# FunControler.net
KiCad netlist of a schematic drawn in EAGLE
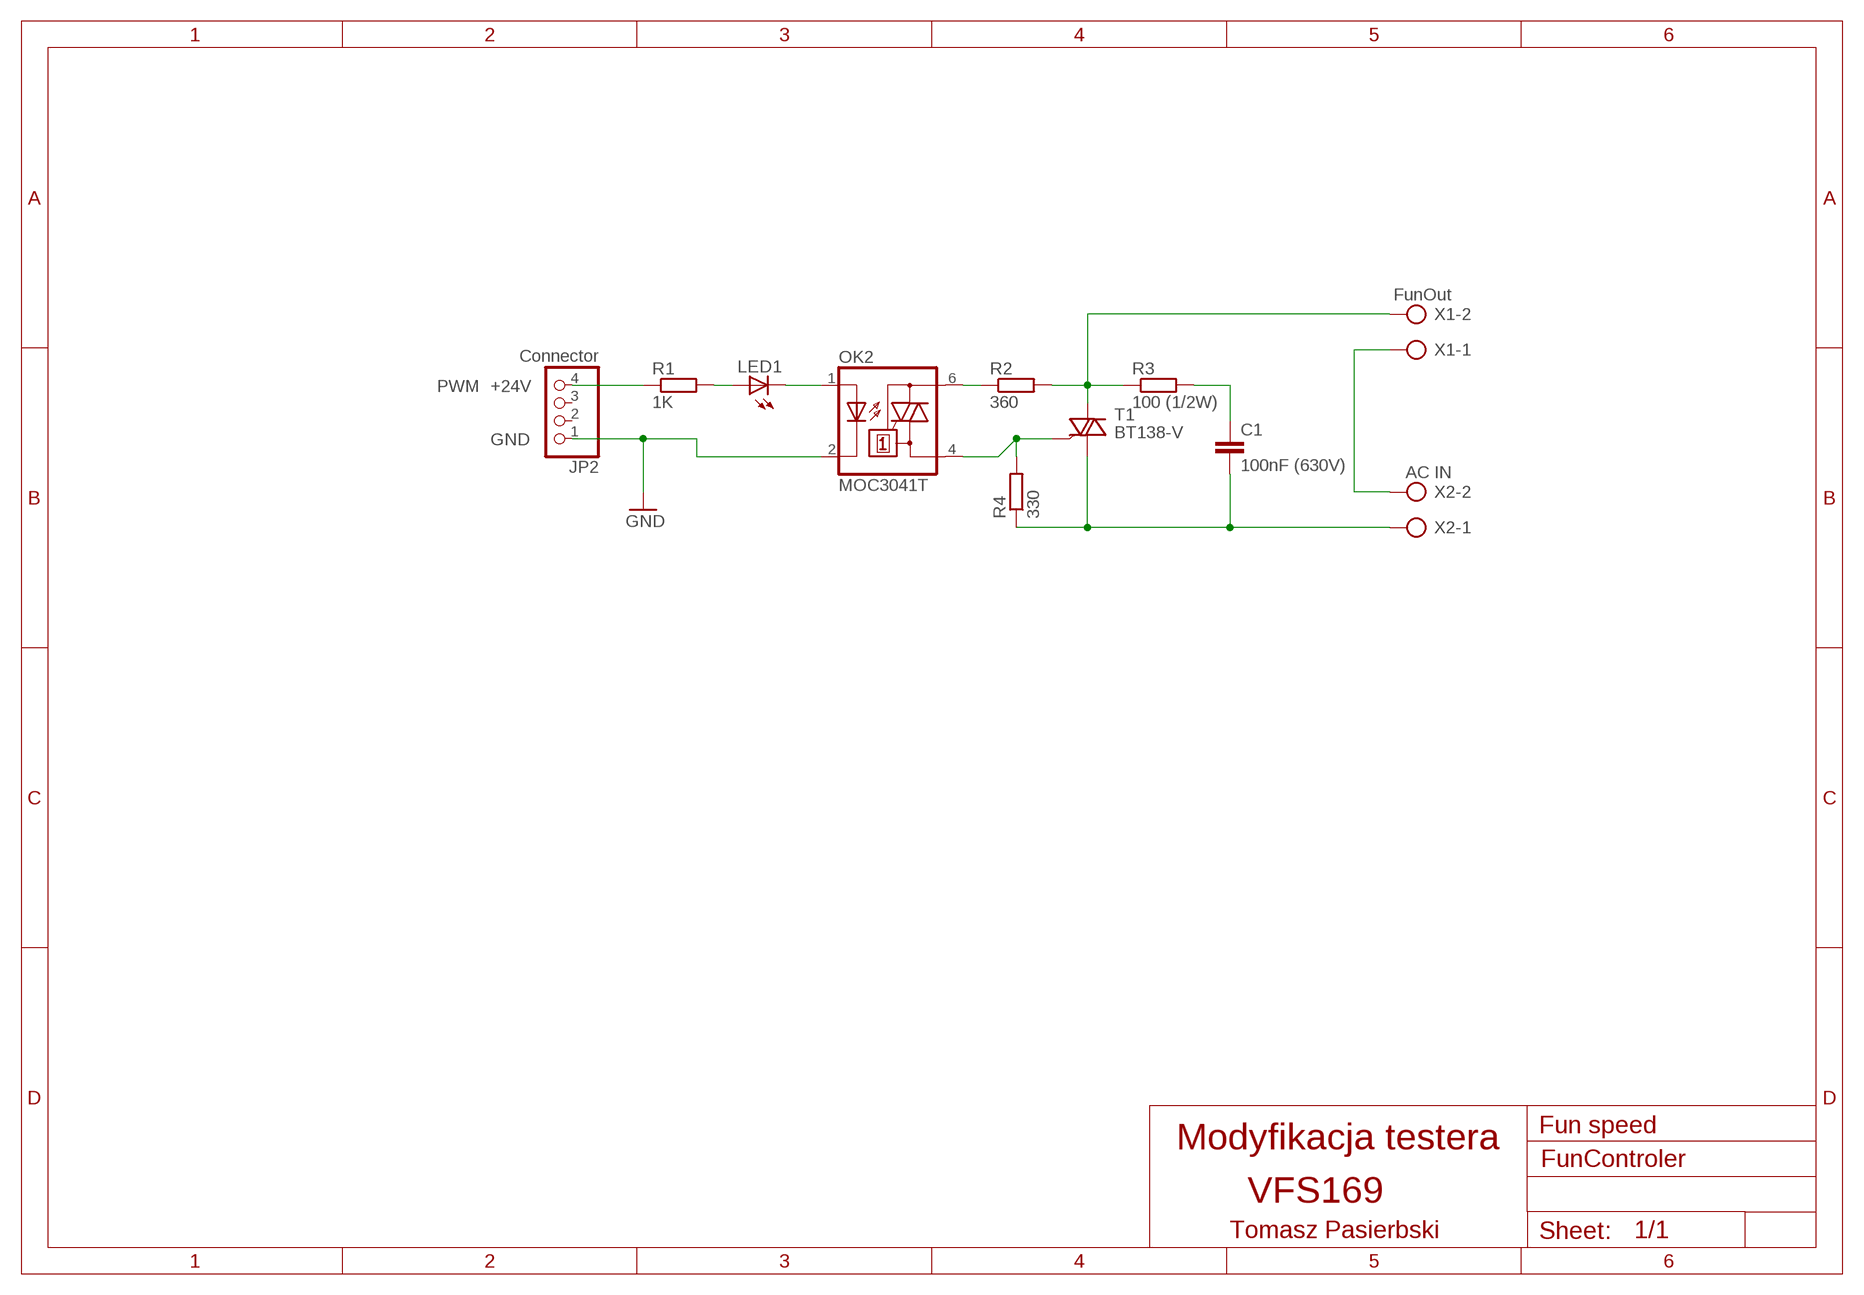
[diagram p0: schematic, sheet 1]

(export (version "E")
  (design (tool "Eeschema 10.0.6"))
  (components
    (comp (ref "C1")
      (value "100nF (630V)")
      (footprint "eagle-import:C075-042X103")
      (libsource (lib "eagle-import") (part "C-EU075-042X103"))
    )
    (comp (ref "JP2")
      (value "Connector")
      (footprint "eagle-import:1X04_90")
      (libsource (lib "eagle-import") (part "PINHD-1X4/90"))
    )
    (comp (ref "LED1")
      (value "LEDSML1206")
      (footprint "eagle-import:SML1206")
      (libsource (lib "eagle-import") (part "LEDSML1206"))
    )
    (comp (ref "OK2")
      (value "MOC3041T")
      (footprint "eagle-import:DIL06B")
      (libsource (lib "eagle-import") (part "MOC30T41"))
    )
    (comp (ref "R1")
      (value "1K")
      (footprint "eagle-import:0207_10")
      (libsource (lib "eagle-import") (part "R-EU_0207/10"))
    )
    (comp (ref "R2")
      (value "360")
      (footprint "eagle-import:0207_10")
      (libsource (lib "eagle-import") (part "R-EU_0207/10"))
    )
    (comp (ref "R3")
      (value "100 (1/2W)")
      (footprint "eagle-import:P0613_15")
      (libsource (lib "eagle-import") (part "R-EU_0613/15"))
    )
    (comp (ref "R4")
      (value "330")
      (footprint "eagle-import:0207_10")
      (libsource (lib "eagle-import") (part "R-EU_0207/10"))
    )
    (comp (ref "T1")
      (value "BT138-V")
      (footprint "eagle-import:TO220BV")
      (libsource (lib "eagle-import") (part "BT138-V"))
    )
    (comp (ref "X1")
      (value "FunOut")
      (footprint "eagle-import:AK300_2")
      (libsource (lib "eagle-import") (part "AK300/2"))
    )
    (comp (ref "X2")
      (value "AC IN")
      (footprint "eagle-import:AK300_2")
      (libsource (lib "eagle-import") (part "AK300/2"))
    )
  )
  (nets
    (net (code "1") (name "GND") (class "Default")
      (node (ref "JP2") (pin "1") (pinfunction "1_1") (pintype "passive"))
      (node (ref "OK2") (pin "2") (pinfunction "C_2") (pintype "passive"))
    )
    (net (code "2") (name "Net-(C1-Pad1)") (class "Default")
      (node (ref "C1") (pin "1") (pinfunction "1_1") (pintype "passive"))
      (node (ref "R3") (pin "2") (pinfunction "2_2") (pintype "passive"))
    )
    (net (code "3") (name "Net-(JP2-Pad4)") (class "Default")
      (node (ref "JP2") (pin "4") (pinfunction "4_4") (pintype "passive"))
      (node (ref "R1") (pin "1") (pinfunction "1_1") (pintype "passive"))
    )
    (net (code "4") (name "Net-(LED1-PadA)") (class "Default")
      (node (ref "LED1") (pin "A") (pinfunction "A_A") (pintype "passive"))
      (node (ref "R1") (pin "2") (pinfunction "2_2") (pintype "passive"))
    )
    (net (code "5") (name "Net-(OK2-A)") (class "Default")
      (node (ref "LED1") (pin "C") (pinfunction "C_C") (pintype "passive"))
      (node (ref "OK2") (pin "1") (pinfunction "A_1") (pintype "passive"))
    )
    (net (code "6") (name "Net-(OK2-A1)") (class "Default")
      (node (ref "OK2") (pin "4") (pinfunction "A1_4") (pintype "passive"))
      (node (ref "R4") (pin "2") (pinfunction "2_2") (pintype "passive"))
      (node (ref "T1") (pin "G") (pinfunction "G_G") (pintype "passive"))
    )
    (net (code "7") (name "Net-(OK2-A2)") (class "Default")
      (node (ref "OK2") (pin "6") (pinfunction "A2_6") (pintype "passive"))
      (node (ref "R2") (pin "1") (pinfunction "1_1") (pintype "passive"))
    )
    (net (code "8") (name "Net-(T1-A1)") (class "Default")
      (node (ref "C1") (pin "2") (pinfunction "2_2") (pintype "passive"))
      (node (ref "R4") (pin "1") (pinfunction "1_1") (pintype "passive"))
      (node (ref "T1") (pin "T1") (pinfunction "A1_T1") (pintype "passive"))
      (node (ref "X2") (pin "1") (pinfunction "KL_1") (pintype "passive"))
    )
    (net (code "9") (name "Net-(T1-A2)") (class "Default")
      (node (ref "R2") (pin "2") (pinfunction "2_2") (pintype "passive"))
      (node (ref "R3") (pin "1") (pinfunction "1_1") (pintype "passive"))
      (node (ref "T1") (pin "T2") (pinfunction "A2_T2") (pintype "passive"))
      (node (ref "X1") (pin "2") (pinfunction "KL_2") (pintype "passive"))
    )
    (net (code "10") (name "Net-(X1A-KL)") (class "Default")
      (node (ref "X1") (pin "1") (pinfunction "KL_1") (pintype "passive"))
      (node (ref "X2") (pin "2") (pinfunction "KL_2") (pintype "passive"))
    )
    (net (code "11") (name "unconnected-(JP2-Pad2)") (class "Default")
      (node (ref "JP2") (pin "2") (pinfunction "2_2") (pintype "passive"))
    )
    (net (code "12") (name "unconnected-(JP2-Pad3)") (class "Default")
      (node (ref "JP2") (pin "3") (pinfunction "3_3") (pintype "passive"))
    )
  )
)
